# CD74HC4067_MUX_5.net
KiCad netlist of a schematic drawn in Altium Designer
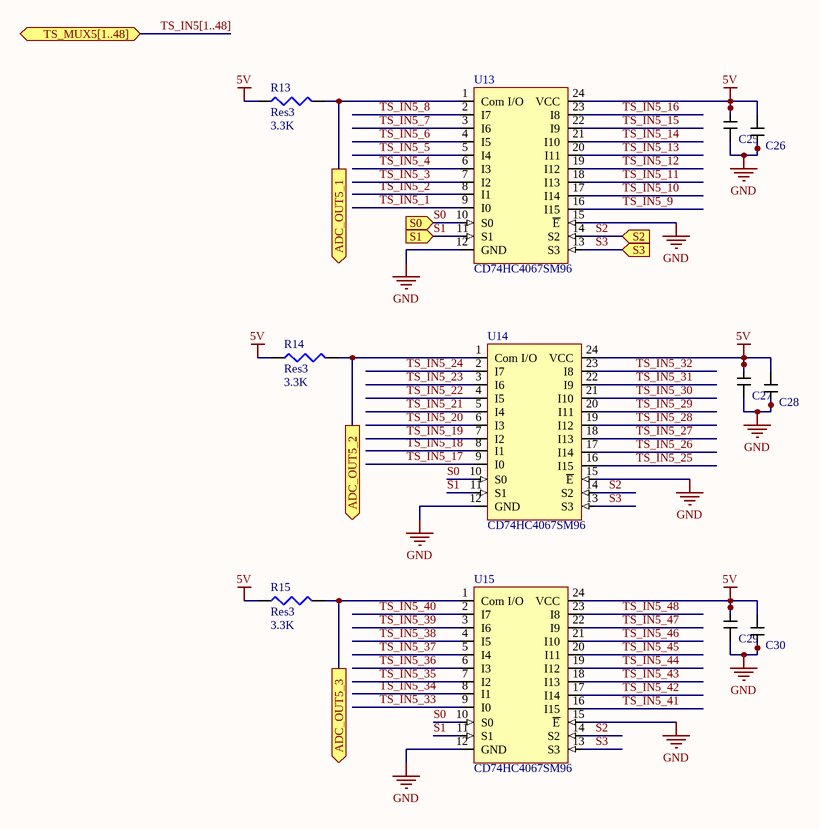
[diagram p0: CD74HC4067_MUX_5.SchDoc]

(export (version "E")
  (design (tool "Eeschema 10.0.6"))
  (components
    (comp (ref "C25")
      (value "0.1uF Cap")
      (footprint "CAPC1608X09M")
      (description "C0603C101K8GAC7867 Kemet Capacitor")
      (libsource (lib "0.1_uF_Kemet_Cap") (part "0.1uF Cap"))
    )
    (comp (ref "C26")
      (value "1uF Samsung Cap")
      (footprint "CAPC1608X09M")
      (libsource (lib "1uF_Samsung_Cap") (part "1uF Samsung Cap"))
    )
    (comp (ref "C27")
      (value "0.1uF Cap")
      (footprint "CAPC1608X09M")
      (description "C0603C101K8GAC7867 Kemet Capacitor")
      (libsource (lib "0.1_uF_Kemet_Cap") (part "0.1uF Cap"))
    )
    (comp (ref "C28")
      (value "1uF Samsung Cap")
      (footprint "CAPC1608X09M")
      (libsource (lib "1uF_Samsung_Cap") (part "1uF Samsung Cap"))
    )
    (comp (ref "C29")
      (value "0.1uF Cap")
      (footprint "CAPC1608X09M")
      (description "C0603C101K8GAC7867 Kemet Capacitor")
      (libsource (lib "0.1_uF_Kemet_Cap") (part "0.1uF Cap"))
    )
    (comp (ref "C30")
      (value "1uF Samsung Cap")
      (footprint "CAPC1608X09M")
      (libsource (lib "1uF_Samsung_Cap") (part "1uF Samsung Cap"))
    )
    (comp (ref "R13")
      (value "Res3")
      (footprint "J1-0603")
      (description "Resistor")
      (fields (field (name "ALTIUM_VALUE") "3.3K") (field (name "PUBLISHER") "Altium Limited"))
      (libsource (lib "Miscellaneous Devices") (part "Res3"))
    )
    (comp (ref "R14")
      (value "Res3")
      (footprint "J1-0603")
      (description "Resistor")
      (fields (field (name "ALTIUM_VALUE") "3.3K") (field (name "PUBLISHER") "Altium Limited"))
      (libsource (lib "Miscellaneous Devices") (part "Res3"))
    )
    (comp (ref "R15")
      (value "Res3")
      (footprint "J1-0603")
      (description "Resistor")
      (fields (field (name "ALTIUM_VALUE") "3.3K") (field (name "PUBLISHER") "Altium Limited"))
      (libsource (lib "Miscellaneous Devices") (part "Res3"))
    )
    (comp (ref "U13")
      (value "CD74HC4067SM96")
      (footprint "SOIC-24_MUX")
      (libsource (lib "TI_Mux") (part "CD74HC4067SM96"))
    )
    (comp (ref "U14")
      (value "CD74HC4067SM96")
      (footprint "SOIC-24_MUX")
      (libsource (lib "TI_Mux") (part "CD74HC4067SM96"))
    )
    (comp (ref "U15")
      (value "CD74HC4067SM96")
      (footprint "SOIC-24_MUX")
      (libsource (lib "TI_Mux") (part "CD74HC4067SM96"))
    )
  )
  (nets
    (net (code "49") (name "/ADC_OUT5_1") (class "Default")
      (node (ref "R13") (pin "2") (pinfunction "2_2") (pintype "passive"))
      (node (ref "U13") (pin "1") (pinfunction "Com_I/O_1") (pintype "bidirectional"))
    )
    (net (code "50") (name "/ADC_OUT5_2") (class "Default")
      (node (ref "R14") (pin "2") (pinfunction "2_2") (pintype "passive"))
      (node (ref "U14") (pin "1") (pinfunction "Com_I/O_1") (pintype "bidirectional"))
    )
    (net (code "51") (name "/ADC_OUT5_3") (class "Default")
      (node (ref "R15") (pin "2") (pinfunction "2_2") (pintype "passive"))
      (node (ref "U15") (pin "1") (pinfunction "Com_I/O_1") (pintype "bidirectional"))
    )
    (net (code "52") (name "/S0") (class "Default")
      (node (ref "U13") (pin "10") (pinfunction "S0_10") (pintype "input"))
      (node (ref "U14") (pin "10") (pinfunction "S0_10") (pintype "input"))
      (node (ref "U15") (pin "10") (pinfunction "S0_10") (pintype "input"))
    )
    (net (code "53") (name "/S1") (class "Default")
      (node (ref "U13") (pin "11") (pinfunction "S1_11") (pintype "input"))
      (node (ref "U14") (pin "11") (pinfunction "S1_11") (pintype "input"))
      (node (ref "U15") (pin "11") (pinfunction "S1_11") (pintype "input"))
    )
    (net (code "54") (name "/S2") (class "Default")
      (node (ref "U13") (pin "14") (pinfunction "S2_14") (pintype "input"))
      (node (ref "U14") (pin "14") (pinfunction "S2_14") (pintype "input"))
      (node (ref "U15") (pin "14") (pinfunction "S2_14") (pintype "input"))
    )
    (net (code "55") (name "/S3") (class "Default")
      (node (ref "U13") (pin "13") (pinfunction "S3_13") (pintype "input"))
      (node (ref "U14") (pin "13") (pinfunction "S3_13") (pintype "input"))
      (node (ref "U15") (pin "13") (pinfunction "S3_13") (pintype "input"))
    )
    (net (code "57") (name "/TS_IN5_1") (class "Default")
      (node (ref "U13") (pin "9") (pinfunction "I0_9") (pintype "passive"))
    )
    (net (code "58") (name "/TS_IN5_2") (class "Default")
      (node (ref "U13") (pin "8") (pinfunction "I1_8") (pintype "passive"))
    )
    (net (code "59") (name "/TS_IN5_3") (class "Default")
      (node (ref "U13") (pin "7") (pinfunction "I2_7") (pintype "passive"))
    )
    (net (code "60") (name "/TS_IN5_4") (class "Default")
      (node (ref "U13") (pin "6") (pinfunction "I3_6") (pintype "passive"))
    )
    (net (code "61") (name "/TS_IN5_5") (class "Default")
      (node (ref "U13") (pin "5") (pinfunction "I4_5") (pintype "passive"))
    )
    (net (code "62") (name "/TS_IN5_6") (class "Default")
      (node (ref "U13") (pin "4") (pinfunction "I5_4") (pintype "passive"))
    )
    (net (code "63") (name "/TS_IN5_7") (class "Default")
      (node (ref "U13") (pin "3") (pinfunction "I6_3") (pintype "passive"))
    )
    (net (code "64") (name "/TS_IN5_8") (class "Default")
      (node (ref "U13") (pin "2") (pinfunction "I7_2") (pintype "passive"))
    )
    (net (code "65") (name "/TS_IN5_9") (class "Default")
      (node (ref "U13") (pin "16") (pinfunction "I15_16") (pintype "passive"))
    )
    (net (code "66") (name "/TS_IN5_10") (class "Default")
      (node (ref "U13") (pin "17") (pinfunction "I14_17") (pintype "passive"))
    )
    (net (code "67") (name "/TS_IN5_11") (class "Default")
      (node (ref "U13") (pin "18") (pinfunction "I13_18") (pintype "passive"))
    )
    (net (code "68") (name "/TS_IN5_12") (class "Default")
      (node (ref "U13") (pin "19") (pinfunction "I12_19") (pintype "passive"))
    )
    (net (code "69") (name "/TS_IN5_13") (class "Default")
      (node (ref "U13") (pin "20") (pinfunction "I11_20") (pintype "passive"))
    )
    (net (code "70") (name "/TS_IN5_14") (class "Default")
      (node (ref "U13") (pin "21") (pinfunction "I10_21") (pintype "passive"))
    )
    (net (code "71") (name "/TS_IN5_15") (class "Default")
      (node (ref "U13") (pin "22") (pinfunction "I9_22") (pintype "passive"))
    )
    (net (code "72") (name "/TS_IN5_16") (class "Default")
      (node (ref "U13") (pin "23") (pinfunction "I8_23") (pintype "passive"))
    )
    (net (code "73") (name "/TS_IN5_17") (class "Default")
      (node (ref "U14") (pin "9") (pinfunction "I0_9") (pintype "passive"))
    )
    (net (code "74") (name "/TS_IN5_18") (class "Default")
      (node (ref "U14") (pin "8") (pinfunction "I1_8") (pintype "passive"))
    )
    (net (code "75") (name "/TS_IN5_19") (class "Default")
      (node (ref "U14") (pin "7") (pinfunction "I2_7") (pintype "passive"))
    )
    (net (code "76") (name "/TS_IN5_20") (class "Default")
      (node (ref "U14") (pin "6") (pinfunction "I3_6") (pintype "passive"))
    )
    (net (code "77") (name "/TS_IN5_21") (class "Default")
      (node (ref "U14") (pin "5") (pinfunction "I4_5") (pintype "passive"))
    )
    (net (code "78") (name "/TS_IN5_22") (class "Default")
      (node (ref "U14") (pin "4") (pinfunction "I5_4") (pintype "passive"))
    )
    (net (code "79") (name "/TS_IN5_23") (class "Default")
      (node (ref "U14") (pin "3") (pinfunction "I6_3") (pintype "passive"))
    )
    (net (code "80") (name "/TS_IN5_24") (class "Default")
      (node (ref "U14") (pin "2") (pinfunction "I7_2") (pintype "passive"))
    )
    (net (code "81") (name "/TS_IN5_25") (class "Default")
      (node (ref "U14") (pin "16") (pinfunction "I15_16") (pintype "passive"))
    )
    (net (code "82") (name "/TS_IN5_26") (class "Default")
      (node (ref "U14") (pin "17") (pinfunction "I14_17") (pintype "passive"))
    )
    (net (code "83") (name "/TS_IN5_27") (class "Default")
      (node (ref "U14") (pin "18") (pinfunction "I13_18") (pintype "passive"))
    )
    (net (code "84") (name "/TS_IN5_28") (class "Default")
      (node (ref "U14") (pin "19") (pinfunction "I12_19") (pintype "passive"))
    )
    (net (code "85") (name "/TS_IN5_29") (class "Default")
      (node (ref "U14") (pin "20") (pinfunction "I11_20") (pintype "passive"))
    )
    (net (code "86") (name "/TS_IN5_30") (class "Default")
      (node (ref "U14") (pin "21") (pinfunction "I10_21") (pintype "passive"))
    )
    (net (code "87") (name "/TS_IN5_31") (class "Default")
      (node (ref "U14") (pin "22") (pinfunction "I9_22") (pintype "passive"))
    )
    (net (code "88") (name "/TS_IN5_32") (class "Default")
      (node (ref "U14") (pin "23") (pinfunction "I8_23") (pintype "passive"))
    )
    (net (code "89") (name "/TS_IN5_33") (class "Default")
      (node (ref "U15") (pin "9") (pinfunction "I0_9") (pintype "passive"))
    )
    (net (code "90") (name "/TS_IN5_34") (class "Default")
      (node (ref "U15") (pin "8") (pinfunction "I1_8") (pintype "passive"))
    )
    (net (code "91") (name "/TS_IN5_35") (class "Default")
      (node (ref "U15") (pin "7") (pinfunction "I2_7") (pintype "passive"))
    )
    (net (code "92") (name "/TS_IN5_36") (class "Default")
      (node (ref "U15") (pin "6") (pinfunction "I3_6") (pintype "passive"))
    )
    (net (code "93") (name "/TS_IN5_37") (class "Default")
      (node (ref "U15") (pin "5") (pinfunction "I4_5") (pintype "passive"))
    )
    (net (code "94") (name "/TS_IN5_38") (class "Default")
      (node (ref "U15") (pin "4") (pinfunction "I5_4") (pintype "passive"))
    )
    (net (code "95") (name "/TS_IN5_39") (class "Default")
      (node (ref "U15") (pin "3") (pinfunction "I6_3") (pintype "passive"))
    )
    (net (code "96") (name "/TS_IN5_40") (class "Default")
      (node (ref "U15") (pin "2") (pinfunction "I7_2") (pintype "passive"))
    )
    (net (code "97") (name "/TS_IN5_41") (class "Default")
      (node (ref "U15") (pin "16") (pinfunction "I15_16") (pintype "passive"))
    )
    (net (code "98") (name "/TS_IN5_42") (class "Default")
      (node (ref "U15") (pin "17") (pinfunction "I14_17") (pintype "passive"))
    )
    (net (code "99") (name "/TS_IN5_43") (class "Default")
      (node (ref "U15") (pin "18") (pinfunction "I13_18") (pintype "passive"))
    )
    (net (code "100") (name "/TS_IN5_44") (class "Default")
      (node (ref "U15") (pin "19") (pinfunction "I12_19") (pintype "passive"))
    )
    (net (code "101") (name "/TS_IN5_45") (class "Default")
      (node (ref "U15") (pin "20") (pinfunction "I11_20") (pintype "passive"))
    )
    (net (code "102") (name "/TS_IN5_46") (class "Default")
      (node (ref "U15") (pin "21") (pinfunction "I10_21") (pintype "passive"))
    )
    (net (code "103") (name "/TS_IN5_47") (class "Default")
      (node (ref "U15") (pin "22") (pinfunction "I9_22") (pintype "passive"))
    )
    (net (code "104") (name "/TS_IN5_48") (class "Default")
      (node (ref "U15") (pin "23") (pinfunction "I8_23") (pintype "passive"))
    )
    (net (code "105") (name "5V") (class "Default")
      (node (ref "C25") (pin "2") (pinfunction "2_2") (pintype "passive"))
      (node (ref "C26") (pin "2") (pinfunction "2_2") (pintype "passive"))
      (node (ref "C27") (pin "2") (pinfunction "2_2") (pintype "passive"))
      (node (ref "C28") (pin "2") (pinfunction "2_2") (pintype "passive"))
      (node (ref "C29") (pin "2") (pinfunction "2_2") (pintype "passive"))
      (node (ref "C30") (pin "2") (pinfunction "2_2") (pintype "passive"))
      (node (ref "R13") (pin "1") (pinfunction "1_1") (pintype "passive"))
      (node (ref "R14") (pin "1") (pinfunction "1_1") (pintype "passive"))
      (node (ref "R15") (pin "1") (pinfunction "1_1") (pintype "passive"))
      (node (ref "U13") (pin "24") (pinfunction "VCC_24") (pintype "power_in"))
      (node (ref "U14") (pin "24") (pinfunction "VCC_24") (pintype "power_in"))
      (node (ref "U15") (pin "24") (pinfunction "VCC_24") (pintype "power_in"))
    )
    (net (code "106") (name "GND") (class "Default")
      (node (ref "C25") (pin "1") (pinfunction "1_1") (pintype "passive"))
      (node (ref "C26") (pin "1") (pinfunction "1_1") (pintype "passive"))
      (node (ref "C27") (pin "1") (pinfunction "1_1") (pintype "passive"))
      (node (ref "C28") (pin "1") (pinfunction "1_1") (pintype "passive"))
      (node (ref "C29") (pin "1") (pinfunction "1_1") (pintype "passive"))
      (node (ref "C30") (pin "1") (pinfunction "1_1") (pintype "passive"))
      (node (ref "U13") (pin "12") (pinfunction "GND_12") (pintype "power_in"))
      (node (ref "U13") (pin "15") (pinfunction "~{E}_15") (pintype "input"))
      (node (ref "U14") (pin "12") (pinfunction "GND_12") (pintype "power_in"))
      (node (ref "U14") (pin "15") (pinfunction "~{E}_15") (pintype "input"))
      (node (ref "U15") (pin "12") (pinfunction "GND_12") (pintype "power_in"))
      (node (ref "U15") (pin "15") (pinfunction "~{E}_15") (pintype "input"))
    )
  )
)
